# SelfTestWiring.net
KiCad netlist of a schematic drawn in EAGLE
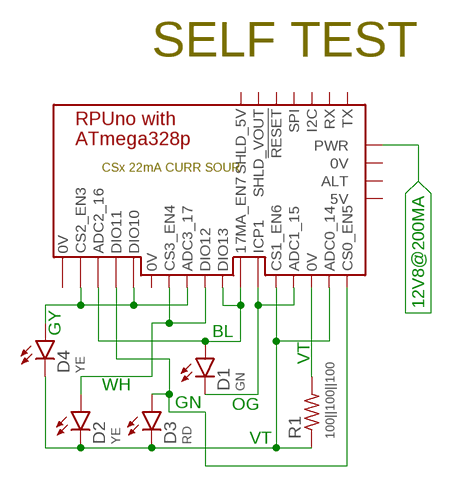
[diagram p0: schematic, sheet 1]

(export (version "E")
  (design (tool "Eeschema 10.0.6"))
  (components
    (comp (ref "BM3")
      (value "RPUNO")
      (footprint "eagle-import:NA-30")
      (libsource (lib "eagle-import") (part "RPUNO"))
    )
    (comp (ref "D1")
      (value "GN")
      (footprint "eagle-import:LED5MM")
      (libsource (lib "eagle-import") (part "LED5MM"))
    )
    (comp (ref "D2")
      (value "YE")
      (footprint "eagle-import:LED5MM")
      (libsource (lib "eagle-import") (part "LED5MM"))
    )
    (comp (ref "D3")
      (value "RD")
      (footprint "eagle-import:LED5MM")
      (libsource (lib "eagle-import") (part "LED5MM"))
    )
    (comp (ref "D4")
      (value "YE")
      (footprint "eagle-import:LED5MM")
      (libsource (lib "eagle-import") (part "LED5MM"))
    )
    (comp (ref "R1")
      (value "100||100||100")
      (footprint "eagle-import:C0805(2012)")
      (libsource (lib "eagle-import") (part "R0805"))
    )
  )
  (nets
    (net (code "1") (name "/BL") (class "Default")
      (node (ref "BM3") (pin "13") (pinfunction "ADC2_16_13") (pintype "bidirectional"))
      (node (ref "BM3") (pin "18") (pinfunction "DIO13_18") (pintype "bidirectional"))
      (node (ref "BM3") (pin "21") (pinfunction "17MA_EN7_21") (pintype "bidirectional"))
      (node (ref "D1") (pin "A") (pinfunction "A_A") (pintype "passive"))
    )
    (net (code "2") (name "/GN") (class "Default")
      (node (ref "BM3") (pin "14") (pinfunction "DIO11_14") (pintype "bidirectional"))
      (node (ref "BM3") (pin "23") (pinfunction "CS0_EN5_23") (pintype "bidirectional"))
      (node (ref "D3") (pin "A") (pinfunction "A_A") (pintype "passive"))
    )
    (net (code "3") (name "/GY") (class "Default")
      (node (ref "BM3") (pin "15") (pinfunction "DIO10_15") (pintype "bidirectional"))
      (node (ref "BM3") (pin "16") (pinfunction "ADC3_17_16") (pintype "bidirectional"))
      (node (ref "BM3") (pin "24") (pinfunction "CS2_EN3_24") (pintype "bidirectional"))
      (node (ref "D4") (pin "A") (pinfunction "A_A") (pintype "passive"))
    )
    (net (code "4") (name "/OG") (class "Default")
      (node (ref "BM3") (pin "10") (pinfunction "ADC1_15_10") (pintype "bidirectional"))
      (node (ref "BM3") (pin "12") (pinfunction "ICP1_12") (pintype "bidirectional"))
      (node (ref "D1") (pin "K") (pinfunction "K_K") (pintype "passive"))
    )
    (net (code "5") (name "/VT") (class "Default")
      (node (ref "BM3") (pin "11") (pinfunction "ADC0_14_11") (pintype "bidirectional"))
      (node (ref "BM3") (pin "22") (pinfunction "CS1_EN6_22") (pintype "bidirectional"))
      (node (ref "D2") (pin "K") (pinfunction "K_K") (pintype "passive"))
      (node (ref "D3") (pin "K") (pinfunction "K_K") (pintype "passive"))
      (node (ref "D4") (pin "K") (pinfunction "K_K") (pintype "passive"))
      (node (ref "R1") (pin "1") (pinfunction "1_1") (pintype "passive"))
    )
    (net (code "6") (name "/WH") (class "Default")
      (node (ref "BM3") (pin "17") (pinfunction "DIO12_17") (pintype "bidirectional"))
      (node (ref "BM3") (pin "29") (pinfunction "CS3_EN4_29") (pintype "bidirectional"))
      (node (ref "D2") (pin "A") (pinfunction "A_A") (pintype "passive"))
    )
    (net (code "7") (name "12V8@200MA") (class "Default")
      (node (ref "BM3") (pin "8") (pinfunction "PWR_8") (pintype "bidirectional"))
    )
    (net (code "8") (name "Net-(BM3-0V-Pad26)") (class "Default")
      (node (ref "BM3") (pin "26") (pinfunction "0V_26") (pintype "bidirectional"))
      (node (ref "R1") (pin "2") (pinfunction "2_2") (pintype "passive"))
    )
    (net (code "9") (name "unconnected-(BM3-0V-Pad9)") (class "Default")
      (node (ref "BM3") (pin "9") (pinfunction "0V_9") (pintype "bidirectional"))
    )
    (net (code "10") (name "unconnected-(BM3-0V-Pad27)") (class "Default")
      (node (ref "BM3") (pin "27") (pinfunction "0V_27") (pintype "bidirectional"))
    )
    (net (code "11") (name "unconnected-(BM3-0V-Pad28)") (class "Default")
      (node (ref "BM3") (pin "28") (pinfunction "0V_28") (pintype "bidirectional"))
    )
    (net (code "12") (name "unconnected-(BM3-5V-Pad19)") (class "Default")
      (node (ref "BM3") (pin "19") (pinfunction "5V_19") (pintype "bidirectional"))
    )
    (net (code "13") (name "unconnected-(BM3-ALT-Pad20)") (class "Default")
      (node (ref "BM3") (pin "20") (pinfunction "ALT_20") (pintype "bidirectional"))
    )
    (net (code "14") (name "unconnected-(BM3-I2C-Pad3)") (class "Default")
      (node (ref "BM3") (pin "3") (pinfunction "I2C_3") (pintype "bidirectional"))
    )
    (net (code "15") (name "unconnected-(BM3-RX-Pad2)") (class "Default")
      (node (ref "BM3") (pin "2") (pinfunction "RX_2") (pintype "bidirectional"))
    )
    (net (code "16") (name "unconnected-(BM3-SHLD_5V-Pad6)") (class "Default")
      (node (ref "BM3") (pin "6") (pinfunction "SHLD_5V_6") (pintype "bidirectional"))
    )
    (net (code "17") (name "unconnected-(BM3-SHLD_VOUT-Pad7)") (class "Default")
      (node (ref "BM3") (pin "7") (pinfunction "SHLD_VOUT_7") (pintype "bidirectional"))
    )
    (net (code "18") (name "unconnected-(BM3-SPI-Pad4)") (class "Default")
      (node (ref "BM3") (pin "4") (pinfunction "SPI_4") (pintype "bidirectional"))
    )
    (net (code "19") (name "unconnected-(BM3-TX-Pad1)") (class "Default")
      (node (ref "BM3") (pin "1") (pinfunction "TX_1") (pintype "bidirectional"))
    )
    (net (code "20") (name "unconnected-(BM3-~{RESET}-Pad5)") (class "Default")
      (node (ref "BM3") (pin "5") (pinfunction "~{RESET}_5") (pintype "bidirectional"))
    )
  )
)
